# Hardwiring.net
KiCad netlist of a schematic drawn in Altium Designer
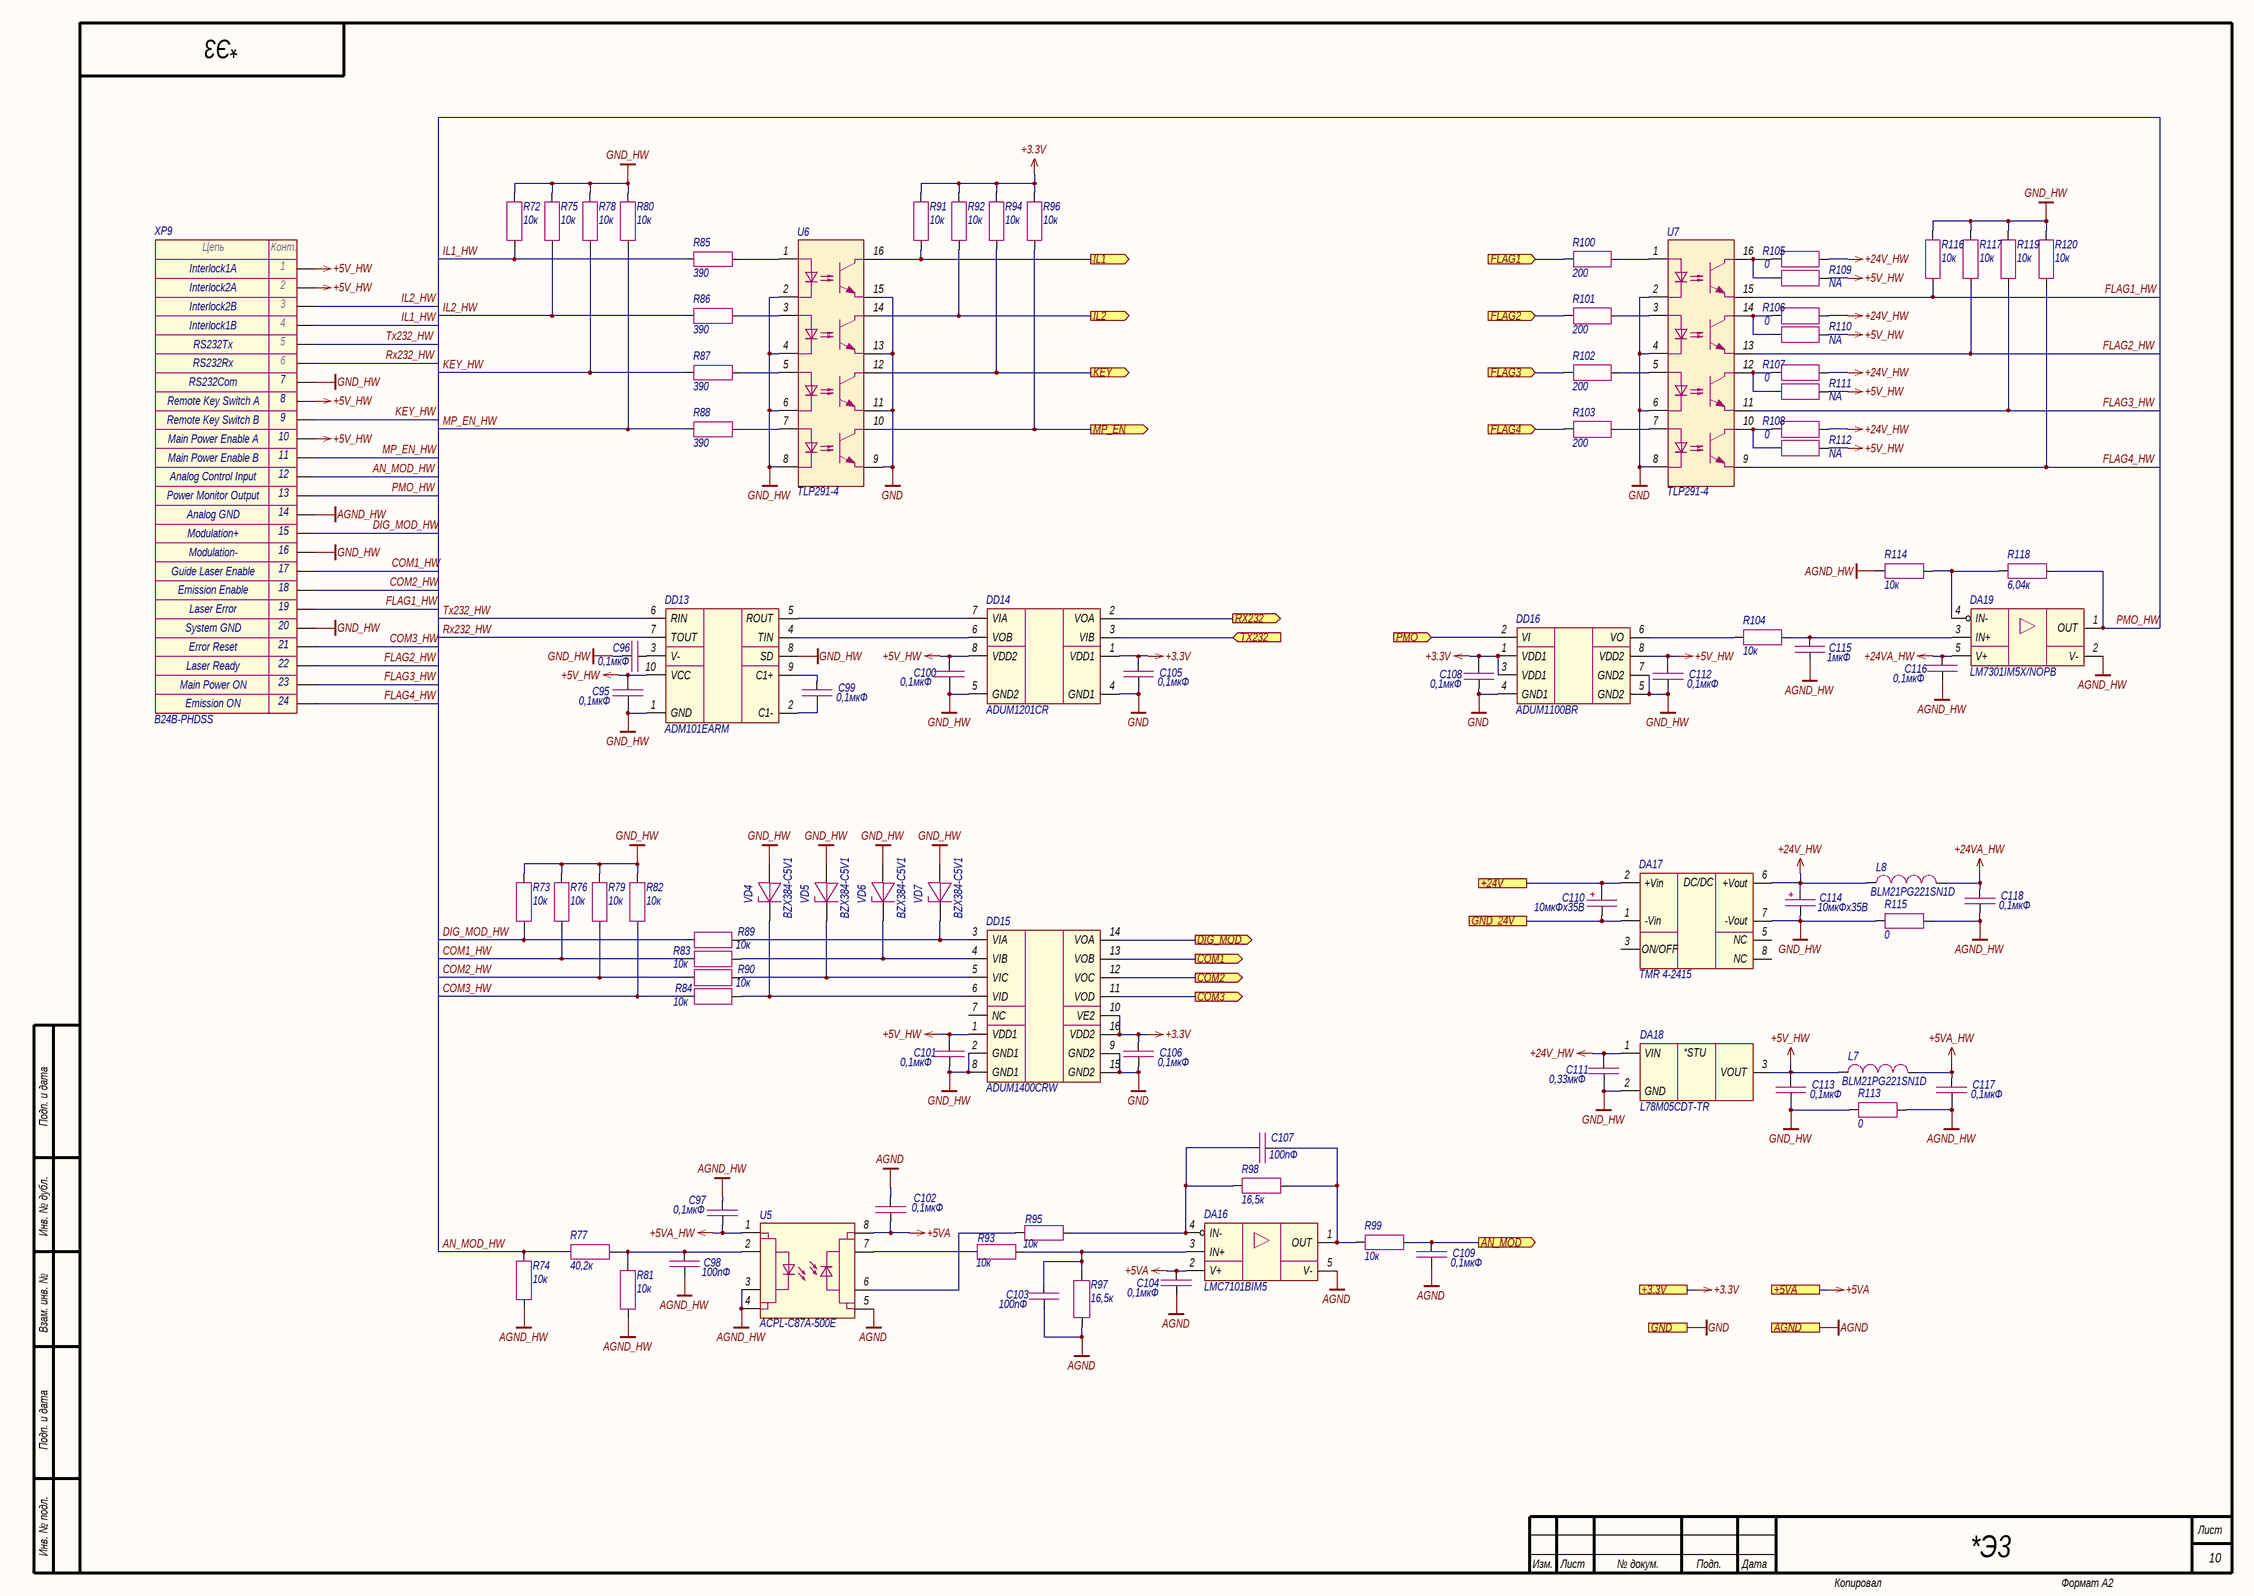
[diagram p0: Hardwiring.SchDoc]

(export (version "E")
  (design (tool "Eeschema 10.0.6"))
  (components
    (comp (ref "C95")
      (value "0,1мкФ")
      (footprint "Pcb_library:CAP_0603")
      (fields (field (name "MANUFACTURER") "Murata"))
      (libsource (lib "Schem_library") (part "Capacitor"))
    )
    (comp (ref "C96")
      (value "0,1мкФ")
      (footprint "Pcb_library:CAP_0603")
      (fields (field (name "MANUFACTURER") "Murata"))
      (libsource (lib "Schem_library") (part "Capacitor"))
    )
    (comp (ref "C97")
      (value "0,1мкФ")
      (footprint "Pcb_library:CAP_0603")
      (fields (field (name "MANUFACTURER") "Murata"))
      (libsource (lib "Schem_library") (part "Capacitor"))
    )
    (comp (ref "C98")
      (value "100пФ")
      (footprint "Pcb_library:CAP_0603")
      (fields (field (name "MANUFACTURER") "Murata"))
      (libsource (lib "Schem_library") (part "Capacitor"))
    )
    (comp (ref "C99")
      (value "0,1мкФ")
      (footprint "Pcb_library:CAP_0603")
      (fields (field (name "MANUFACTURER") "Murata"))
      (libsource (lib "Schem_library") (part "Capacitor"))
    )
    (comp (ref "C100")
      (value "0,1мкФ")
      (footprint "Pcb_library:CAP_0603")
      (fields (field (name "MANUFACTURER") "Murata"))
      (libsource (lib "Schem_library") (part "Capacitor"))
    )
    (comp (ref "C101")
      (value "0,1мкФ")
      (footprint "Pcb_library:CAP_0603")
      (fields (field (name "MANUFACTURER") "Murata"))
      (libsource (lib "Schem_library") (part "Capacitor"))
    )
    (comp (ref "C102")
      (value "0,1мкФ")
      (footprint "Pcb_library:CAP_0603")
      (fields (field (name "MANUFACTURER") "Murata"))
      (libsource (lib "Schem_library") (part "Capacitor"))
    )
    (comp (ref "C103")
      (value "100пФ")
      (footprint "Pcb_library:CAP_0603")
      (fields (field (name "MANUFACTURER") "Murata"))
      (libsource (lib "Schem_library") (part "Capacitor"))
    )
    (comp (ref "C104")
      (value "0,1мкФ")
      (footprint "Pcb_library:CAP_0603")
      (fields (field (name "MANUFACTURER") "Murata"))
      (libsource (lib "Schem_library") (part "Capacitor"))
    )
    (comp (ref "C105")
      (value "0,1мкФ")
      (footprint "Pcb_library:CAP_0603")
      (fields (field (name "MANUFACTURER") "Murata"))
      (libsource (lib "Schem_library") (part "Capacitor"))
    )
    (comp (ref "C106")
      (value "0,1мкФ")
      (footprint "Pcb_library:CAP_0603")
      (fields (field (name "MANUFACTURER") "Murata"))
      (libsource (lib "Schem_library") (part "Capacitor"))
    )
    (comp (ref "C107")
      (value "100пФ")
      (footprint "Pcb_library:CAP_0603")
      (fields (field (name "MANUFACTURER") "Murata"))
      (libsource (lib "Schem_library") (part "Capacitor"))
    )
    (comp (ref "C108")
      (value "0,1мкФ")
      (footprint "Pcb_library:CAP_0603")
      (fields (field (name "MANUFACTURER") "Murata"))
      (libsource (lib "Schem_library") (part "Capacitor"))
    )
    (comp (ref "C109")
      (value "0,1мкФ")
      (footprint "Pcb_library:CAP_0603")
      (fields (field (name "MANUFACTURER") "Murata"))
      (libsource (lib "Schem_library") (part "Capacitor"))
    )
    (comp (ref "C110")
      (value "10мкФх35B")
      (footprint "Pcb_library:CAP_C")
      (libsource (lib "") (part "Capacitor_Polar_1"))
    )
    (comp (ref "C111")
      (value "0,33мкФ")
      (footprint "Pcb_library:CAP_0805")
      (fields (field (name "MANUFACTURER") "Murata"))
      (libsource (lib "Schem_library") (part "Capacitor"))
    )
    (comp (ref "C112")
      (value "0,1мкФ")
      (footprint "Pcb_library:CAP_0603")
      (fields (field (name "MANUFACTURER") "Murata"))
      (libsource (lib "Schem_library") (part "Capacitor"))
    )
    (comp (ref "C113")
      (value "0,1мкФ")
      (footprint "Pcb_library:CAP_0603")
      (fields (field (name "MANUFACTURER") "Murata"))
      (libsource (lib "Schem_library") (part "Capacitor"))
    )
    (comp (ref "C114")
      (value "10мкФх35B")
      (footprint "Pcb_library:CAP_C")
      (libsource (lib "Schem_library") (part "Capacitor_Polar"))
    )
    (comp (ref "C115")
      (value "1мкФ")
      (footprint "Pcb_library:CAP_0603")
      (fields (field (name "MANUFACTURER") "Murata"))
      (libsource (lib "Schem_library") (part "Capacitor"))
    )
    (comp (ref "C116")
      (value "0,1мкФ")
      (footprint "Pcb_library:CAP_0603")
      (fields (field (name "MANUFACTURER") "Murata"))
      (libsource (lib "Schem_library") (part "Capacitor"))
    )
    (comp (ref "C117")
      (value "0,1мкФ")
      (footprint "Pcb_library:CAP_0603")
      (fields (field (name "MANUFACTURER") "Murata"))
      (libsource (lib "Schem_library") (part "Capacitor"))
    )
    (comp (ref "C118")
      (value "0,1мкФ")
      (footprint "Pcb_library:CAP_0603")
      (fields (field (name "MANUFACTURER") "Murata"))
      (libsource (lib "Schem_library") (part "Capacitor"))
    )
    (comp (ref "DA16")
      (value "LMC7101BIM5")
      (footprint "Pcb_library:SOT-23-5")
      (fields (field (name "MANUFACTURER") "Texas Instruments"))
      (libsource (lib "Schem_library") (part "LMC7101"))
    )
    (comp (ref "DA17")
      (value "TMR 4-2415")
      (footprint "Pcb_library:TMR4 (SIP-8)")
      (fields (field (name "MANUFACTURER") "Traco Power"))
      (libsource (lib "Schem_library") (part "TMR4"))
    )
    (comp (ref "DA18")
      (value "L78M05CDT-TR")
      (footprint "Pcb_library:TO-252")
      (fields (field (name "MANUFACTURER") "STMicroelectronics"))
      (libsource (lib "Schem_library") (part "L78M"))
    )
    (comp (ref "DA19")
      (value "LM7301IM5X/NOPB")
      (footprint "Pcb_library:SOT-23-5")
      (fields (field (name "MANUFACTURER") "Texas Instruments"))
      (libsource (lib "Schem_library") (part "LM7301IM5"))
    )
    (comp (ref "DD13")
      (value "ADM101EARM")
      (footprint "Pcb_library:MSOP-10")
      (fields (field (name "MANUFACTURER") "Analog Devices"))
      (libsource (lib "Schem_library") (part "ADM101EARM"))
    )
    (comp (ref "DD14")
      (value "ADUM1201CR")
      (footprint "Pcb_library:SOIC-8")
      (fields (field (name "MANUFACTURER") "Analog Devices"))
      (libsource (lib "Schem_library") (part "ADUM1201"))
    )
    (comp (ref "DD15")
      (value "ADUM1400CRW")
      (footprint "Pcb_library:SOIC-16W")
      (fields (field (name "MANUFACTURER") "Analog Devices"))
      (libsource (lib "Schem_library") (part "ADUM1400"))
    )
    (comp (ref "DD16")
      (value "ADUM1100BR")
      (footprint "Pcb_library:SOIC-8")
      (fields (field (name "MANUFACTURER") "Analog Devices"))
      (libsource (lib "Schem_library") (part "ADUM1100"))
    )
    (comp (ref "L7")
      (value "BLM21PG221SN1D")
      (footprint "Pcb_library:IND_0805")
      (fields (field (name "MANUFACTURER") "Murata"))
      (libsource (lib "Schem_library") (part "Inductor"))
    )
    (comp (ref "L8")
      (value "BLM21PG221SN1D")
      (footprint "Pcb_library:IND_0805")
      (fields (field (name "MANUFACTURER") "Murata"))
      (libsource (lib "Schem_library") (part "Inductor"))
    )
    (comp (ref "R72")
      (value "10к")
      (footprint "Pcb_library:RES_0603")
      (fields (field (name "MANUFACTURER") "Yageo"))
      (libsource (lib "Schem_library") (part "Resistor"))
    )
    (comp (ref "R73")
      (value "10к")
      (footprint "Pcb_library:RES_0603")
      (fields (field (name "MANUFACTURER") "Yageo"))
      (libsource (lib "Schem_library") (part "Resistor"))
    )
    (comp (ref "R74")
      (value "10к")
      (footprint "Pcb_library:RES_0603")
      (fields (field (name "MANUFACTURER") "Yageo"))
      (libsource (lib "Schem_library") (part "Resistor"))
    )
    (comp (ref "R75")
      (value "10к")
      (footprint "Pcb_library:RES_0603")
      (fields (field (name "MANUFACTURER") "Yageo"))
      (libsource (lib "Schem_library") (part "Resistor"))
    )
    (comp (ref "R76")
      (value "10к")
      (footprint "Pcb_library:RES_0603")
      (fields (field (name "MANUFACTURER") "Yageo"))
      (libsource (lib "Schem_library") (part "Resistor"))
    )
    (comp (ref "R77")
      (value "40,2к")
      (footprint "Pcb_library:RES_0603")
      (fields (field (name "MANUFACTURER") "Yageo"))
      (libsource (lib "Schem_library") (part "Resistor"))
    )
    (comp (ref "R78")
      (value "10к")
      (footprint "Pcb_library:RES_0603")
      (fields (field (name "MANUFACTURER") "Yageo"))
      (libsource (lib "Schem_library") (part "Resistor"))
    )
    (comp (ref "R79")
      (value "10к")
      (footprint "Pcb_library:RES_0603")
      (fields (field (name "MANUFACTURER") "Yageo"))
      (libsource (lib "Schem_library") (part "Resistor"))
    )
    (comp (ref "R80")
      (value "10к")
      (footprint "Pcb_library:RES_0603")
      (fields (field (name "MANUFACTURER") "Yageo"))
      (libsource (lib "Schem_library") (part "Resistor"))
    )
    (comp (ref "R81")
      (value "10к")
      (footprint "Pcb_library:RES_0603")
      (fields (field (name "MANUFACTURER") "Yageo"))
      (libsource (lib "Schem_library") (part "Resistor"))
    )
    (comp (ref "R82")
      (value "10к")
      (footprint "Pcb_library:RES_0603")
      (fields (field (name "MANUFACTURER") "Yageo"))
      (libsource (lib "Schem_library") (part "Resistor"))
    )
    (comp (ref "R83")
      (value "10к")
      (footprint "Pcb_library:RES_0603")
      (fields (field (name "MANUFACTURER") "Yageo"))
      (libsource (lib "Schem_library") (part "Resistor"))
    )
    (comp (ref "R84")
      (value "10к")
      (footprint "Pcb_library:RES_0603")
      (fields (field (name "MANUFACTURER") "Yageo"))
      (libsource (lib "Schem_library") (part "Resistor"))
    )
    (comp (ref "R85")
      (value "390")
      (footprint "Pcb_library:RES_0603")
      (fields (field (name "MANUFACTURER") "Yageo"))
      (libsource (lib "Schem_library") (part "Resistor"))
    )
    (comp (ref "R86")
      (value "390")
      (footprint "Pcb_library:RES_0603")
      (fields (field (name "MANUFACTURER") "Yageo"))
      (libsource (lib "Schem_library") (part "Resistor"))
    )
    (comp (ref "R87")
      (value "390")
      (footprint "Pcb_library:RES_0603")
      (fields (field (name "MANUFACTURER") "Yageo"))
      (libsource (lib "Schem_library") (part "Resistor"))
    )
    (comp (ref "R88")
      (value "390")
      (footprint "Pcb_library:RES_0603")
      (fields (field (name "MANUFACTURER") "Yageo"))
      (libsource (lib "Schem_library") (part "Resistor"))
    )
    (comp (ref "R89")
      (value "10к")
      (footprint "Pcb_library:RES_0603")
      (fields (field (name "MANUFACTURER") "Yageo"))
      (libsource (lib "Schem_library") (part "Resistor"))
    )
    (comp (ref "R90")
      (value "10к")
      (footprint "Pcb_library:RES_0603")
      (fields (field (name "MANUFACTURER") "Yageo"))
      (libsource (lib "Schem_library") (part "Resistor"))
    )
    (comp (ref "R91")
      (value "10к")
      (footprint "Pcb_library:RES_0603")
      (fields (field (name "MANUFACTURER") "Yageo"))
      (libsource (lib "Schem_library") (part "Resistor"))
    )
    (comp (ref "R92")
      (value "10к")
      (footprint "Pcb_library:RES_0603")
      (fields (field (name "MANUFACTURER") "Yageo"))
      (libsource (lib "Schem_library") (part "Resistor"))
    )
    (comp (ref "R93")
      (value "10к")
      (footprint "Pcb_library:RES_0603")
      (fields (field (name "MANUFACTURER") "Yageo"))
      (libsource (lib "Schem_library") (part "Resistor"))
    )
    (comp (ref "R94")
      (value "10к")
      (footprint "Pcb_library:RES_0603")
      (fields (field (name "MANUFACTURER") "Yageo"))
      (libsource (lib "Schem_library") (part "Resistor"))
    )
    (comp (ref "R95")
      (value "10к")
      (footprint "Pcb_library:RES_0603")
      (fields (field (name "MANUFACTURER") "Yageo"))
      (libsource (lib "Schem_library") (part "Resistor"))
    )
    (comp (ref "R96")
      (value "10к")
      (footprint "Pcb_library:RES_0603")
      (fields (field (name "MANUFACTURER") "Yageo"))
      (libsource (lib "Schem_library") (part "Resistor"))
    )
    (comp (ref "R97")
      (value "16,5к")
      (footprint "Pcb_library:RES_0603")
      (fields (field (name "MANUFACTURER") "Yageo"))
      (libsource (lib "Schem_library") (part "Resistor"))
    )
    (comp (ref "R98")
      (value "16,5к")
      (footprint "Pcb_library:RES_0603")
      (fields (field (name "MANUFACTURER") "Yageo"))
      (libsource (lib "Schem_library") (part "Resistor"))
    )
    (comp (ref "R99")
      (value "10к")
      (footprint "Pcb_library:RES_0603")
      (fields (field (name "MANUFACTURER") "Yageo"))
      (libsource (lib "Schem_library") (part "Resistor"))
    )
    (comp (ref "R100")
      (value "200")
      (footprint "Pcb_library:RES_0603")
      (fields (field (name "MANUFACTURER") "Yageo"))
      (libsource (lib "Schem_library") (part "Resistor"))
    )
    (comp (ref "R101")
      (value "200")
      (footprint "Pcb_library:RES_0603")
      (fields (field (name "MANUFACTURER") "Yageo"))
      (libsource (lib "Schem_library") (part "Resistor"))
    )
    (comp (ref "R102")
      (value "200")
      (footprint "Pcb_library:RES_0603")
      (fields (field (name "MANUFACTURER") "Yageo"))
      (libsource (lib "Schem_library") (part "Resistor"))
    )
    (comp (ref "R103")
      (value "200")
      (footprint "Pcb_library:RES_0603")
      (fields (field (name "MANUFACTURER") "Yageo"))
      (libsource (lib "Schem_library") (part "Resistor"))
    )
    (comp (ref "R104")
      (value "10к")
      (footprint "Pcb_library:RES_0603")
      (fields (field (name "MANUFACTURER") "Yageo"))
      (libsource (lib "Schem_library") (part "Resistor"))
    )
    (comp (ref "R105")
      (value "0")
      (footprint "Pcb_library:RES_0603")
      (fields (field (name "MANUFACTURER") "Yageo"))
      (libsource (lib "Schem_library") (part "Resistor"))
    )
    (comp (ref "R106")
      (value "0")
      (footprint "Pcb_library:RES_0603")
      (fields (field (name "MANUFACTURER") "Yageo"))
      (libsource (lib "Schem_library") (part "Resistor"))
    )
    (comp (ref "R107")
      (value "0")
      (footprint "Pcb_library:RES_0603")
      (fields (field (name "MANUFACTURER") "Yageo"))
      (libsource (lib "Schem_library") (part "Resistor"))
    )
    (comp (ref "R108")
      (value "0")
      (footprint "Pcb_library:RES_0603")
      (fields (field (name "MANUFACTURER") "Yageo"))
      (libsource (lib "Schem_library") (part "Resistor"))
    )
    (comp (ref "R109")
      (value "NA")
      (footprint "Pcb_library:RES_0603")
      (libsource (lib "Schem_library") (part "Resistor"))
    )
    (comp (ref "R110")
      (value "NA")
      (footprint "Pcb_library:RES_0603")
      (libsource (lib "Schem_library") (part "Resistor"))
    )
    (comp (ref "R111")
      (value "NA")
      (footprint "Pcb_library:RES_0603")
      (libsource (lib "Schem_library") (part "Resistor"))
    )
    (comp (ref "R112")
      (value "NA")
      (footprint "Pcb_library:RES_0603")
      (libsource (lib "Schem_library") (part "Resistor"))
    )
    (comp (ref "R113")
      (value "0")
      (footprint "Pcb_library:RES_0805")
      (fields (field (name "MANUFACTURER") "Yageo"))
      (libsource (lib "Schem_library") (part "Resistor"))
    )
    (comp (ref "R114")
      (value "10к")
      (footprint "Pcb_library:RES_0603")
      (fields (field (name "MANUFACTURER") "Yageo"))
      (libsource (lib "Schem_library") (part "Resistor"))
    )
    (comp (ref "R115")
      (value "0")
      (footprint "Pcb_library:RES_0805")
      (fields (field (name "MANUFACTURER") "Yageo"))
      (libsource (lib "Schem_library") (part "Resistor"))
    )
    (comp (ref "R116")
      (value "10к")
      (footprint "Pcb_library:RES_0603")
      (fields (field (name "MANUFACTURER") "Yageo"))
      (libsource (lib "Schem_library") (part "Resistor"))
    )
    (comp (ref "R117")
      (value "10к")
      (footprint "Pcb_library:RES_0603")
      (fields (field (name "MANUFACTURER") "Yageo"))
      (libsource (lib "Schem_library") (part "Resistor"))
    )
    (comp (ref "R118")
      (value "6,04к")
      (footprint "Pcb_library:RES_0603")
      (fields (field (name "MANUFACTURER") "Yageo"))
      (libsource (lib "Schem_library") (part "Resistor"))
    )
    (comp (ref "R119")
      (value "10к")
      (footprint "Pcb_library:RES_0603")
      (fields (field (name "MANUFACTURER") "Yageo"))
      (libsource (lib "Schem_library") (part "Resistor"))
    )
    (comp (ref "R120")
      (value "10к")
      (footprint "Pcb_library:RES_0603")
      (fields (field (name "MANUFACTURER") "Yageo"))
      (libsource (lib "Schem_library") (part "Resistor"))
    )
    (comp (ref "U5")
      (value "ACPL-C87A-500E")
      (footprint "Pcb_library:SSO-8")
      (fields (field (name "MANUFACTURER") "Broadcom"))
      (libsource (lib "Schem_library") (part "ACPL-C87"))
    )
    (comp (ref "U6")
      (value "TLP291-4")
      (footprint "Pcb_library:SOP-16")
      (fields (field (name "MANUFACTURER") "Toshiba"))
      (libsource (lib "Schem_library") (part "TLP281-4"))
    )
    (comp (ref "U7")
      (value "TLP291-4")
      (footprint "Pcb_library:SOP-16")
      (fields (field (name "MANUFACTURER") "Toshiba"))
      (libsource (lib "Schem_library") (part "TLP281-4"))
    )
    (comp (ref "VD4")
      (value "BZX384-C5V1")
      (footprint "Pcb_library:SOD-323")
      (fields (field (name "MANUFACTURER") "Nexperia"))
      (libsource (lib "Schem_library") (part "Diode_Zener"))
    )
    (comp (ref "VD5")
      (value "BZX384-C5V1")
      (footprint "Pcb_library:SOD-323")
      (fields (field (name "MANUFACTURER") "Nexperia"))
      (libsource (lib "Schem_library") (part "Diode_Zener"))
    )
    (comp (ref "VD6")
      (value "BZX384-C5V1")
      (footprint "Pcb_library:SOD-323")
      (fields (field (name "MANUFACTURER") "Nexperia"))
      (libsource (lib "Schem_library") (part "Diode_Zener"))
    )
    (comp (ref "VD7")
      (value "BZX384-C5V1")
      (footprint "Pcb_library:SOD-323")
      (fields (field (name "MANUFACTURER") "Nexperia"))
      (libsource (lib "Schem_library") (part "Diode_Zener"))
    )
    (comp (ref "XP9")
      (value "B24B-PHDSS")
      (footprint "Pcb_library:B24B-PHDSS")
      (fields (field (name "MANUFACTURER") "JST"))
      (libsource (lib "Schem_library") (part "Connector-24"))
    )
  )
  (nets
    (net (code "1") (name "+3.3V") (class "Default")
      (node (ref "C105") (pin "1") (pinfunction "1_1") (pintype "passive"))
      (node (ref "C106") (pin "1") (pinfunction "1_1") (pintype "passive"))
      (node (ref "C108") (pin "1") (pinfunction "1_1") (pintype "passive"))
      (node (ref "DD14") (pin "1") (pinfunction "VDD1_1") (pintype "passive"))
      (node (ref "DD15") (pin "10") (pinfunction "VE2_10") (pintype "passive"))
      (node (ref "DD15") (pin "16") (pinfunction "VDD2_16") (pintype "passive"))
      (node (ref "DD16") (pin "1") (pinfunction "VDD1_1") (pintype "passive"))
      (node (ref "DD16") (pin "3") (pinfunction "VDD1_3") (pintype "passive"))
      (node (ref "R91") (pin "1") (pinfunction "1_1") (pintype "passive"))
      (node (ref "R92") (pin "1") (pinfunction "1_1") (pintype "passive"))
      (node (ref "R94") (pin "1") (pinfunction "1_1") (pintype "passive"))
      (node (ref "R96") (pin "1") (pinfunction "1_1") (pintype "passive"))
    )
    (net (code "2") (name "+5VA") (class "Default")
      (node (ref "C102") (pin "1") (pinfunction "1_1") (pintype "passive"))
      (node (ref "C104") (pin "1") (pinfunction "1_1") (pintype "passive"))
      (node (ref "DA16") (pin "2") (pinfunction "V+_2") (pintype "passive"))
      (node (ref "U5") (pin "8") (pinfunction "VDD2_8") (pintype "passive"))
    )
    (net (code "3") (name "+5VA_HW") (class "Default")
      (node (ref "C117") (pin "1") (pinfunction "1_1") (pintype "passive"))
      (node (ref "C97") (pin "1") (pinfunction "1_1") (pintype "passive"))
      (node (ref "L7") (pin "2") (pinfunction "2_2") (pintype "passive"))
      (node (ref "U5") (pin "1") (pinfunction "VDD1_1") (pintype "passive"))
    )
    (net (code "4") (name "+5V_HW") (class "Default")
      (node (ref "C100") (pin "1") (pinfunction "1_1") (pintype "passive"))
      (node (ref "C101") (pin "1") (pinfunction "1_1") (pintype "passive"))
      (node (ref "C112") (pin "1") (pinfunction "1_1") (pintype "passive"))
      (node (ref "C113") (pin "1") (pinfunction "1_1") (pintype "passive"))
      (node (ref "C95") (pin "1") (pinfunction "1_1") (pintype "passive"))
      (node (ref "DA18") (pin "3") (pinfunction "VOUT_3") (pintype "passive"))
      (node (ref "DD13") (pin "10") (pinfunction "VCC_10") (pintype "passive"))
      (node (ref "DD14") (pin "8") (pinfunction "VDD2_8") (pintype "passive"))
      (node (ref "DD15") (pin "1") (pinfunction "VDD1_1") (pintype "passive"))
      (node (ref "DD16") (pin "8") (pinfunction "VDD2_8") (pintype "passive"))
      (node (ref "L7") (pin "1") (pinfunction "1_1") (pintype "passive"))
      (node (ref "R109") (pin "2") (pinfunction "2_2") (pintype "passive"))
      (node (ref "R110") (pin "2") (pinfunction "2_2") (pintype "passive"))
      (node (ref "R111") (pin "2") (pinfunction "2_2") (pintype "passive"))
      (node (ref "R112") (pin "2") (pinfunction "2_2") (pintype "passive"))
      (node (ref "XP9") (pin "1") (pintype "passive"))
      (node (ref "XP9") (pin "10") (pintype "passive"))
      (node (ref "XP9") (pin "2") (pintype "passive"))
      (node (ref "XP9") (pin "8") (pintype "passive"))
    )
    (net (code "5") (name "+24VA_HW") (class "Default")
      (node (ref "C116") (pin "1") (pinfunction "1_1") (pintype "passive"))
      (node (ref "C118") (pin "1") (pinfunction "1_1") (pintype "passive"))
      (node (ref "DA19") (pin "5") (pinfunction "V+_5") (pintype "passive"))
      (node (ref "L8") (pin "2") (pinfunction "2_2") (pintype "passive"))
    )
    (net (code "6") (name "+24V_HW") (class "Default")
      (node (ref "C111") (pin "2") (pinfunction "2_2") (pintype "passive"))
      (node (ref "C114") (pin "1") (pinfunction "1_1") (pintype "passive"))
      (node (ref "DA17") (pin "6") (pinfunction "+Vout_6") (pintype "passive"))
      (node (ref "DA18") (pin "1") (pinfunction "VIN_1") (pintype "passive"))
      (node (ref "L8") (pin "1") (pinfunction "1_1") (pintype "passive"))
      (node (ref "R105") (pin "2") (pinfunction "2_2") (pintype "passive"))
      (node (ref "R106") (pin "2") (pinfunction "2_2") (pintype "passive"))
      (node (ref "R107") (pin "2") (pinfunction "2_2") (pintype "passive"))
      (node (ref "R108") (pin "2") (pinfunction "2_2") (pintype "passive"))
    )
    (net (code "7") (name "/+24V") (class "Default")
      (node (ref "C110") (pin "1") (pinfunction "1_1") (pintype "passive"))
      (node (ref "DA17") (pin "2") (pinfunction "+Vin_2") (pintype "passive"))
    )
    (net (code "8") (name "/AN_MOD") (class "Default")
      (node (ref "C109") (pin "1") (pinfunction "1_1") (pintype "passive"))
      (node (ref "R99") (pin "2") (pinfunction "2_2") (pintype "passive"))
    )
    (net (code "9") (name "/AN_MOD_HW") (class "Default")
      (node (ref "R74") (pin "1") (pinfunction "1_1") (pintype "passive"))
      (node (ref "R77") (pin "2") (pinfunction "2_2") (pintype "passive"))
      (node (ref "XP9") (pin "12") (pintype "passive"))
    )
    (net (code "10") (name "/COM1") (class "Default")
      (node (ref "DD15") (pin "13") (pinfunction "VOB_13") (pintype "passive"))
    )
    (net (code "11") (name "/COM1_HW") (class "Default")
      (node (ref "R76") (pin "2") (pinfunction "2_2") (pintype "passive"))
      (node (ref "R83") (pin "1") (pinfunction "1_1") (pintype "passive"))
      (node (ref "XP9") (pin "17") (pintype "passive"))
    )
    (net (code "12") (name "/COM2") (class "Default")
      (node (ref "DD15") (pin "12") (pinfunction "VOC_12") (pintype "passive"))
    )
    (net (code "13") (name "/COM2_HW") (class "Default")
      (node (ref "R79") (pin "2") (pinfunction "2_2") (pintype "passive"))
      (node (ref "R90") (pin "1") (pinfunction "1_1") (pintype "passive"))
      (node (ref "XP9") (pin "18") (pintype "passive"))
    )
    (net (code "14") (name "/COM3") (class "Default")
      (node (ref "DD15") (pin "11") (pinfunction "VOD_11") (pintype "passive"))
    )
    (net (code "15") (name "/COM3_HW") (class "Default")
      (node (ref "R82") (pin "2") (pinfunction "2_2") (pintype "passive"))
      (node (ref "R84") (pin "1") (pinfunction "1_1") (pintype "passive"))
      (node (ref "XP9") (pin "21") (pintype "passive"))
    )
    (net (code "16") (name "/DIG_MOD") (class "Default")
      (node (ref "DD15") (pin "14") (pinfunction "VOA_14") (pintype "passive"))
    )
    (net (code "17") (name "/DIG_MOD_HW") (class "Default")
      (node (ref "R73") (pin "2") (pinfunction "2_2") (pintype "passive"))
      (node (ref "R89") (pin "1") (pinfunction "1_1") (pintype "passive"))
      (node (ref "XP9") (pin "15") (pintype "passive"))
    )
    (net (code "18") (name "/FLAG1") (class "Default")
      (node (ref "R100") (pin "2") (pinfunction "2_2") (pintype "passive"))
    )
    (net (code "19") (name "/FLAG1_HW") (class "Default")
      (node (ref "R116") (pin "2") (pinfunction "2_2") (pintype "passive"))
      (node (ref "U7") (pin "15") (pintype "passive"))
      (node (ref "XP9") (pin "19") (pintype "passive"))
    )
    (net (code "20") (name "/FLAG2") (class "Default")
      (node (ref "R101") (pin "2") (pinfunction "2_2") (pintype "passive"))
    )
    (net (code "21") (name "/FLAG2_HW") (class "Default")
      (node (ref "R117") (pin "2") (pinfunction "2_2") (pintype "passive"))
      (node (ref "U7") (pin "13") (pintype "passive"))
      (node (ref "XP9") (pin "22") (pintype "passive"))
    )
    (net (code "22") (name "/FLAG3") (class "Default")
      (node (ref "R102") (pin "2") (pinfunction "2_2") (pintype "passive"))
    )
    (net (code "23") (name "/FLAG3_HW") (class "Default")
      (node (ref "R119") (pin "2") (pinfunction "2_2") (pintype "passive"))
      (node (ref "U7") (pin "11") (pintype "passive"))
      (node (ref "XP9") (pin "23") (pintype "passive"))
    )
    (net (code "24") (name "/FLAG4") (class "Default")
      (node (ref "R103") (pin "2") (pinfunction "2_2") (pintype "passive"))
    )
    (net (code "25") (name "/FLAG4_HW") (class "Default")
      (node (ref "R120") (pin "2") (pinfunction "2_2") (pintype "passive"))
      (node (ref "U7") (pin "9") (pintype "passive"))
      (node (ref "XP9") (pin "24") (pintype "passive"))
    )
    (net (code "26") (name "/GND_24V") (class "Default")
      (node (ref "C110") (pin "2") (pinfunction "2_2") (pintype "passive"))
      (node (ref "DA17") (pin "1") (pinfunction "-Vin_1") (pintype "passive"))
    )
    (net (code "27") (name "/IL1") (class "Default")
      (node (ref "R91") (pin "2") (pinfunction "2_2") (pintype "passive"))
      (node (ref "U6") (pin "16") (pintype "passive"))
    )
    (net (code "28") (name "/IL1_HW") (class "Default")
      (node (ref "R72") (pin "2") (pinfunction "2_2") (pintype "passive"))
      (node (ref "R85") (pin "1") (pinfunction "1_1") (pintype "passive"))
      (node (ref "XP9") (pin "4") (pintype "passive"))
    )
    (net (code "29") (name "/IL2") (class "Default")
      (node (ref "R92") (pin "2") (pinfunction "2_2") (pintype "passive"))
      (node (ref "U6") (pin "14") (pintype "passive"))
    )
    (net (code "30") (name "/IL2_HW") (class "Default")
      (node (ref "R75") (pin "2") (pinfunction "2_2") (pintype "passive"))
      (node (ref "R86") (pin "1") (pinfunction "1_1") (pintype "passive"))
      (node (ref "XP9") (pin "3") (pintype "passive"))
    )
    (net (code "31") (name "/KEY") (class "Default")
      (node (ref "R94") (pin "2") (pinfunction "2_2") (pintype "passive"))
      (node (ref "U6") (pin "12") (pintype "passive"))
    )
    (net (code "32") (name "/KEY_HW") (class "Default")
      (node (ref "R78") (pin "2") (pinfunction "2_2") (pintype "passive"))
      (node (ref "R87") (pin "1") (pinfunction "1_1") (pintype "passive"))
      (node (ref "XP9") (pin "9") (pintype "passive"))
    )
    (net (code "33") (name "/MP_EN") (class "Default")
      (node (ref "R96") (pin "2") (pinfunction "2_2") (pintype "passive"))
      (node (ref "U6") (pin "10") (pintype "passive"))
    )
    (net (code "34") (name "/MP_EN_HW") (class "Default")
      (node (ref "R80") (pin "2") (pinfunction "2_2") (pintype "passive"))
      (node (ref "R88") (pin "1") (pinfunction "1_1") (pintype "passive"))
      (node (ref "XP9") (pin "11") (pintype "passive"))
    )
    (net (code "35") (name "/PMO") (class "Default")
      (node (ref "DD16") (pin "2") (pinfunction "VI_2") (pintype "passive"))
    )
    (net (code "36") (name "/PMO_HW") (class "Default")
      (node (ref "DA19") (pin "1") (pinfunction "OUT_1") (pintype "passive"))
      (node (ref "R118") (pin "2") (pinfunction "2_2") (pintype "passive"))
      (node (ref "XP9") (pin "13") (pintype "passive"))
    )
    (net (code "37") (name "/RX232") (class "Default")
      (node (ref "DD14") (pin "2") (pinfunction "VOA_2") (pintype "passive"))
    )
    (net (code "38") (name "/Rx232_HW") (class "Default")
      (node (ref "DD13") (pin "7") (pinfunction "TOUT_7") (pintype "passive"))
      (node (ref "XP9") (pin "6") (pintype "passive"))
    )
    (net (code "39") (name "/TX232") (class "Default")
      (node (ref "DD14") (pin "3") (pinfunction "VIB_3") (pintype "passive"))
    )
    (net (code "40") (name "/Tx232_HW") (class "Default")
      (node (ref "DD13") (pin "6") (pinfunction "RIN_6") (pintype "passive"))
      (node (ref "XP9") (pin "5") (pintype "passive"))
    )
    (net (code "41") (name "AGND") (class "Default")
      (node (ref "C102") (pin "2") (pinfunction "2_2") (pintype "passive"))
      (node (ref "C103") (pin "2") (pinfunction "2_2") (pintype "passive"))
      (node (ref "C104") (pin "2") (pinfunction "2_2") (pintype "passive"))
      (node (ref "C109") (pin "2") (pinfunction "2_2") (pintype "passive"))
      (node (ref "DA16") (pin "5") (pinfunction "V-_5") (pintype "passive"))
      (node (ref "R97") (pin "2") (pinfunction "2_2") (pintype "passive"))
      (node (ref "U5") (pin "5") (pinfunction "GND2_5") (pintype "passive"))
    )
    (net (code "42") (name "AGND_HW") (class "Default")
      (node (ref "C115") (pin "2") (pinfunction "2_2") (pintype "passive"))
      (node (ref "C116") (pin "2") (pinfunction "2_2") (pintype "passive"))
      (node (ref "C117") (pin "2") (pinfunction "2_2") (pintype "passive"))
      (node (ref "C118") (pin "2") (pinfunction "2_2") (pintype "passive"))
      (node (ref "C97") (pin "2") (pinfunction "2_2") (pintype "passive"))
      (node (ref "C98") (pin "1") (pinfunction "1_1") (pintype "passive"))
      (node (ref "DA19") (pin "2") (pinfunction "V-_2") (pintype "passive"))
      (node (ref "R113") (pin "2") (pinfunction "2_2") (pintype "passive"))
      (node (ref "R114") (pin "1") (pinfunction "1_1") (pintype "passive"))
      (node (ref "R115") (pin "2") (pinfunction "2_2") (pintype "passive"))
      (node (ref "R74") (pin "2") (pinfunction "2_2") (pintype "passive"))
      (node (ref "R81") (pin "2") (pinfunction "2_2") (pintype "passive"))
      (node (ref "U5") (pin "3") (pinfunction "SHDN_3") (pintype "passive"))
      (node (ref "U5") (pin "4") (pinfunction "GND1_4") (pintype "passive"))
      (node (ref "XP9") (pin "14") (pintype "passive"))
    )
    (net (code "43") (name "GND") (class "Default")
      (node (ref "C105") (pin "2") (pinfunction "2_2") (pintype "passive"))
      (node (ref "C106") (pin "2") (pinfunction "2_2") (pintype "passive"))
      (node (ref "C108") (pin "2") (pinfunction "2_2") (pintype "passive"))
      (node (ref "DD14") (pin "4") (pinfunction "GND1_4") (pintype "passive"))
      (node (ref "DD15") (pin "15") (pinfunction "GND2_15") (pintype "passive"))
      (node (ref "DD15") (pin "9") (pinfunction "GND2_9") (pintype "passive"))
      (node (ref "DD16") (pin "4") (pinfunction "GND1_4") (pintype "passive"))
      (node (ref "U6") (pin "11") (pintype "passive"))
      (node (ref "U6") (pin "13") (pintype "passive"))
      (node (ref "U6") (pin "15") (pintype "passive"))
      (node (ref "U6") (pin "9") (pintype "passive"))
      (node (ref "U7") (pin "2") (pintype "passive"))
      (node (ref "U7") (pin "4") (pintype "passive"))
      (node (ref "U7") (pin "6") (pintype "passive"))
      (node (ref "U7") (pin "8") (pintype "passive"))
    )
    (net (code "44") (name "GND_HW") (class "Default")
      (node (ref "C100") (pin "2") (pinfunction "2_2") (pintype "passive"))
      (node (ref "C101") (pin "2") (pinfunction "2_2") (pintype "passive"))
      (node (ref "C111") (pin "1") (pinfunction "1_1") (pintype "passive"))
      (node (ref "C112") (pin "2") (pinfunction "2_2") (pintype "passive"))
      (node (ref "C113") (pin "2") (pinfunction "2_2") (pintype "passive"))
      (node (ref "C114") (pin "2") (pinfunction "2_2") (pintype "passive"))
      (node (ref "C95") (pin "2") (pinfunction "2_2") (pintype "passive"))
      (node (ref "C96") (pin "2") (pinfunction "2_2") (pintype "passive"))
      (node (ref "DA17") (pin "7") (pinfunction "-Vout_7") (pintype "passive"))
      (node (ref "DA18") (pin "2") (pinfunction "GND_2") (pintype "passive"))
      (node (ref "DD13") (pin "1") (pinfunction "GND_1") (pintype "passive"))
      (node (ref "DD13") (pin "8") (pinfunction "SD_8") (pintype "passive"))
      (node (ref "DD14") (pin "5") (pinfunction "GND2_5") (pintype "passive"))
      (node (ref "DD15") (pin "2") (pinfunction "GND1_2") (pintype "passive"))
      (node (ref "DD15") (pin "8") (pinfunction "GND1_8") (pintype "passive"))
      (node (ref "DD16") (pin "5") (pinfunction "GND2_5") (pintype "passive"))
      (node (ref "DD16") (pin "7") (pinfunction "GND2_7") (pintype "passive"))
      (node (ref "R113") (pin "1") (pinfunction "1_1") (pintype "passive"))
      (node (ref "R115") (pin "1") (pinfunction "1_1") (pintype "passive"))
      (node (ref "R116") (pin "1") (pinfunction "1_1") (pintype "passive"))
      (node (ref "R117") (pin "1") (pinfunction "1_1") (pintype "passive"))
      (node (ref "R119") (pin "1") (pinfunction "1_1") (pintype "passive"))
      (node (ref "R120") (pin "1") (pinfunction "1_1") (pintype "passive"))
      (node (ref "R72") (pin "1") (pinfunction "1_1") (pintype "passive"))
      (node (ref "R73") (pin "1") (pinfunction "1_1") (pintype "passive"))
      (node (ref "R75") (pin "1") (pinfunction "1_1") (pintype "passive"))
      (node (ref "R76") (pin "1") (pinfunction "1_1") (pintype "passive"))
      (node (ref "R78") (pin "1") (pinfunction "1_1") (pintype "passive"))
      (node (ref "R79") (pin "1") (pinfunction "1_1") (pintype "passive"))
      (node (ref "R80") (pin "1") (pinfunction "1_1") (pintype "passive"))
      (node (ref "R82") (pin "1") (pinfunction "1_1") (pintype "passive"))
      (node (ref "U6") (pin "2") (pintype "passive"))
      (node (ref "U6") (pin "4") (pintype "passive"))
      (node (ref "U6") (pin "6") (pintype "passive"))
      (node (ref "U6") (pin "8") (pintype "passive"))
      (node (ref "VD4") (pin "2") (pinfunction "A_2") (pintype "passive"))
      (node (ref "VD5") (pin "2") (pinfunction "A_2") (pintype "passive"))
      (node (ref "VD6") (pin "2") (pinfunction "A_2") (pintype "passive"))
      (node (ref "VD7") (pin "2") (pinfunction "A_2") (pintype "passive"))
      (node (ref "XP9") (pin "16") (pintype "passive"))
      (node (ref "XP9") (pin "20") (pintype "passive"))
      (node (ref "XP9") (pin "7") (pintype "passive"))
    )
    (net (code "45") (name "Net-(DA16-IN+)") (class "Default")
      (node (ref "C103") (pin "1") (pinfunction "1_1") (pintype "passive"))
      (node (ref "DA16") (pin "3") (pinfunction "IN+_3") (pintype "passive"))
      (node (ref "R93") (pin "2") (pinfunction "2_2") (pintype "passive"))
      (node (ref "R97") (pin "1") (pinfunction "1_1") (pintype "passive"))
    )
    (net (code "46") (name "Net-(DA16-IN-)") (class "Default")
      (node (ref "C107") (pin "1") (pinfunction "1_1") (pintype "passive"))
      (node (ref "DA16") (pin "4") (pinfunction "IN-_4") (pintype "passive"))
      (node (ref "R95") (pin "2") (pinfunction "2_2") (pintype "passive"))
      (node (ref "R98") (pin "2") (pinfunction "2_2") (pintype "passive"))
    )
    (net (code "47") (name "Net-(DA16-OUT)") (class "Default")
      (node (ref "C107") (pin "2") (pinfunction "2_2") (pintype "passive"))
      (node (ref "DA16") (pin "1") (pinfunction "OUT_1") (pintype "passive"))
      (node (ref "R98") (pin "1") (pinfunction "1_1") (pintype "passive"))
      (node (ref "R99") (pin "1") (pinfunction "1_1") (pintype "passive"))
    )
    (net (code "48") (name "Net-(DA19-IN+)") (class "Default")
      (node (ref "C115") (pin "1") (pinfunction "1_1") (pintype "passive"))
      (node (ref "DA19") (pin "3") (pinfunction "IN+_3") (pintype "passive"))
      (node (ref "R104") (pin "2") (pinfunction "2_2") (pintype "passive"))
    )
    (net (code "49") (name "Net-(DA19-IN-)") (class "Default")
      (node (ref "DA19") (pin "4") (pinfunction "IN-_4") (pintype "passive"))
      (node (ref "R114") (pin "2") (pinfunction "2_2") (pintype "passive"))
      (node (ref "R118") (pin "1") (pinfunction "1_1") (pintype "passive"))
    )
    (net (code "50") (name "Net-(DD13-C1+)") (class "Default")
      (node (ref "C99") (pin "1") (pinfunction "1_1") (pintype "passive"))
      (node (ref "DD13") (pin "9") (pinfunction "C1+_9") (pintype "passive"))
    )
    (net (code "51") (name "Net-(DD13-C1-)") (class "Default")
      (node (ref "C99") (pin "2") (pinfunction "2_2") (pintype "passive"))
      (node (ref "DD13") (pin "2") (pinfunction "C1-_2") (pintype "passive"))
    )
    (net (code "52") (name "Net-(DD13-ROUT)") (class "Default")
      (node (ref "DD13") (pin "5") (pinfunction "ROUT_5") (pintype "passive"))
      (node (ref "DD14") (pin "7") (pinfunction "VIA_7") (pintype "passive"))
    )
    (net (code "53") (name "Net-(DD13-TIN)") (class "Default")
      (node (ref "DD13") (pin "4") (pinfunction "TIN_4") (pintype "passive"))
      (node (ref "DD14") (pin "6") (pinfunction "VOB_6") (pintype "passive"))
    )
    (net (code "54") (name "Net-(DD13-V-)") (class "Default")
      (node (ref "C96") (pin "1") (pinfunction "1_1") (pintype "passive"))
      (node (ref "DD13") (pin "3") (pinfunction "V-_3") (pintype "passive"))
    )
    (net (code "55") (name "Net-(DD15-VIA)") (class "Default")
      (node (ref "DD15") (pin "3") (pinfunction "VIA_3") (pintype "passive"))
      (node (ref "R89") (pin "2") (pinfunction "2_2") (pintype "passive"))
      (node (ref "VD7") (pin "1") (pinfunction "K_1") (pintype "passive"))
    )
    (net (code "56") (name "Net-(DD15-VIB)") (class "Default")
      (node (ref "DD15") (pin "4") (pinfunction "VIB_4") (pintype "passive"))
      (node (ref "R83") (pin "2") (pinfunction "2_2") (pintype "passive"))
      (node (ref "VD6") (pin "1") (pinfunction "K_1") (pintype "passive"))
    )
    (net (code "57") (name "Net-(DD15-VIC)") (class "Default")
      (node (ref "DD15") (pin "5") (pinfunction "VIC_5") (pintype "passive"))
      (node (ref "R90") (pin "2") (pinfunction "2_2") (pintype "passive"))
      (node (ref "VD5") (pin "1") (pinfunction "K_1") (pintype "passive"))
    )
    (net (code "58") (name "Net-(DD15-VID)") (class "Default")
      (node (ref "DD15") (pin "6") (pinfunction "VID_6") (pintype "passive"))
      (node (ref "R84") (pin "2") (pinfunction "2_2") (pintype "passive"))
      (node (ref "VD4") (pin "1") (pinfunction "K_1") (pintype "passive"))
    )
    (net (code "59") (name "Net-(DD16-VO)") (class "Default")
      (node (ref "DD16") (pin "6") (pinfunction "VO_6") (pintype "passive"))
      (node (ref "R104") (pin "1") (pinfunction "1_1") (pintype "passive"))
    )
    (net (code "60") (name "Net-(R85-Pad2)") (class "Default")
      (node (ref "R85") (pin "2") (pinfunction "2_2") (pintype "passive"))
      (node (ref "U6") (pin "1") (pintype "passive"))
    )
    (net (code "61") (name "Net-(R86-Pad2)") (class "Default")
      (node (ref "R86") (pin "2") (pinfunction "2_2") (pintype "passive"))
      (node (ref "U6") (pin "3") (pintype "passive"))
    )
    (net (code "62") (name "Net-(R87-Pad2)") (class "Default")
      (node (ref "R87") (pin "2") (pinfunction "2_2") (pintype "passive"))
      (node (ref "U6") (pin "5") (pintype "passive"))
    )
    (net (code "63") (name "Net-(R88-Pad2)") (class "Default")
      (node (ref "R88") (pin "2") (pinfunction "2_2") (pintype "passive"))
      (node (ref "U6") (pin "7") (pintype "passive"))
    )
    (net (code "64") (name "Net-(R100-Pad1)") (class "Default")
      (node (ref "R100") (pin "1") (pinfunction "1_1") (pintype "passive"))
      (node (ref "U7") (pin "1") (pintype "passive"))
    )
    (net (code "65") (name "Net-(R101-Pad1)") (class "Default")
      (node (ref "R101") (pin "1") (pinfunction "1_1") (pintype "passive"))
      (node (ref "U7") (pin "3") (pintype "passive"))
    )
    (net (code "66") (name "Net-(R102-Pad1)") (class "Default")
      (node (ref "R102") (pin "1") (pinfunction "1_1") (pintype "passive"))
      (node (ref "U7") (pin "5") (pintype "passive"))
    )
    (net (code "67") (name "Net-(R103-Pad1)") (class "Default")
      (node (ref "R103") (pin "1") (pinfunction "1_1") (pintype "passive"))
      (node (ref "U7") (pin "7") (pintype "passive"))
    )
    (net (code "68") (name "Net-(R105-Pad1)") (class "Default")
      (node (ref "R105") (pin "1") (pinfunction "1_1") (pintype "passive"))
      (node (ref "R109") (pin "1") (pinfunction "1_1") (pintype "passive"))
      (node (ref "U7") (pin "16") (pintype "passive"))
    )
    (net (code "69") (name "Net-(R106-Pad1)") (class "Default")
      (node (ref "R106") (pin "1") (pinfunction "1_1") (pintype "passive"))
      (node (ref "R110") (pin "1") (pinfunction "1_1") (pintype "passive"))
      (node (ref "U7") (pin "14") (pintype "passive"))
    )
    (net (code "70") (name "Net-(R107-Pad1)") (class "Default")
      (node (ref "R107") (pin "1") (pinfunction "1_1") (pintype "passive"))
      (node (ref "R111") (pin "1") (pinfunction "1_1") (pintype "passive"))
      (node (ref "U7") (pin "12") (pintype "passive"))
    )
    (net (code "71") (name "Net-(R108-Pad1)") (class "Default")
      (node (ref "R108") (pin "1") (pinfunction "1_1") (pintype "passive"))
      (node (ref "R112") (pin "1") (pinfunction "1_1") (pintype "passive"))
      (node (ref "U7") (pin "10") (pintype "passive"))
    )
    (net (code "72") (name "Net-(U5-VIN)") (class "Default")
      (node (ref "C98") (pin "2") (pinfunction "2_2") (pintype "passive"))
      (node (ref "R77") (pin "1") (pinfunction "1_1") (pintype "passive"))
      (node (ref "R81") (pin "1") (pinfunction "1_1") (pintype "passive"))
      (node (ref "U5") (pin "2") (pinfunction "VIN_2") (pintype "passive"))
    )
    (net (code "73") (name "Net-(U5-VOUT+)") (class "Default")
      (node (ref "R93") (pin "1") (pinfunction "1_1") (pintype "passive"))
      (node (ref "U5") (pin "7") (pinfunction "VOUT+_7") (pintype "passive"))
    )
    (net (code "74") (name "Net-(U5-VOUT-)") (class "Default")
      (node (ref "R95") (pin "1") (pinfunction "1_1") (pintype "passive"))
      (node (ref "U5") (pin "6") (pinfunction "VOUT-_6") (pintype "passive"))
    )
    (net (code "75") (name "unconnected-(DA17-NC-Pad5)") (class "Default")
      (node (ref "DA17") (pin "5") (pinfunction "NC_5") (pintype "passive"))
    )
    (net (code "76") (name "unconnected-(DA17-NC-Pad8)") (class "Default")
      (node (ref "DA17") (pin "8") (pinfunction "NC_8") (pintype "passive"))
    )
    (net (code "77") (name "unconnected-(DA17-ON{slash}OFF-Pad3)") (class "Default")
      (node (ref "DA17") (pin "3") (pinfunction "ON/OFF_3") (pintype "passive"))
    )
    (net (code "78") (name "unconnected-(DD15-NC-Pad7)") (class "Default")
      (node (ref "DD15") (pin "7") (pinfunction "NC_7") (pintype "passive"))
    )
  )
)
